# M100X.net
KiCad netlist of a schematic drawn in EAGLE
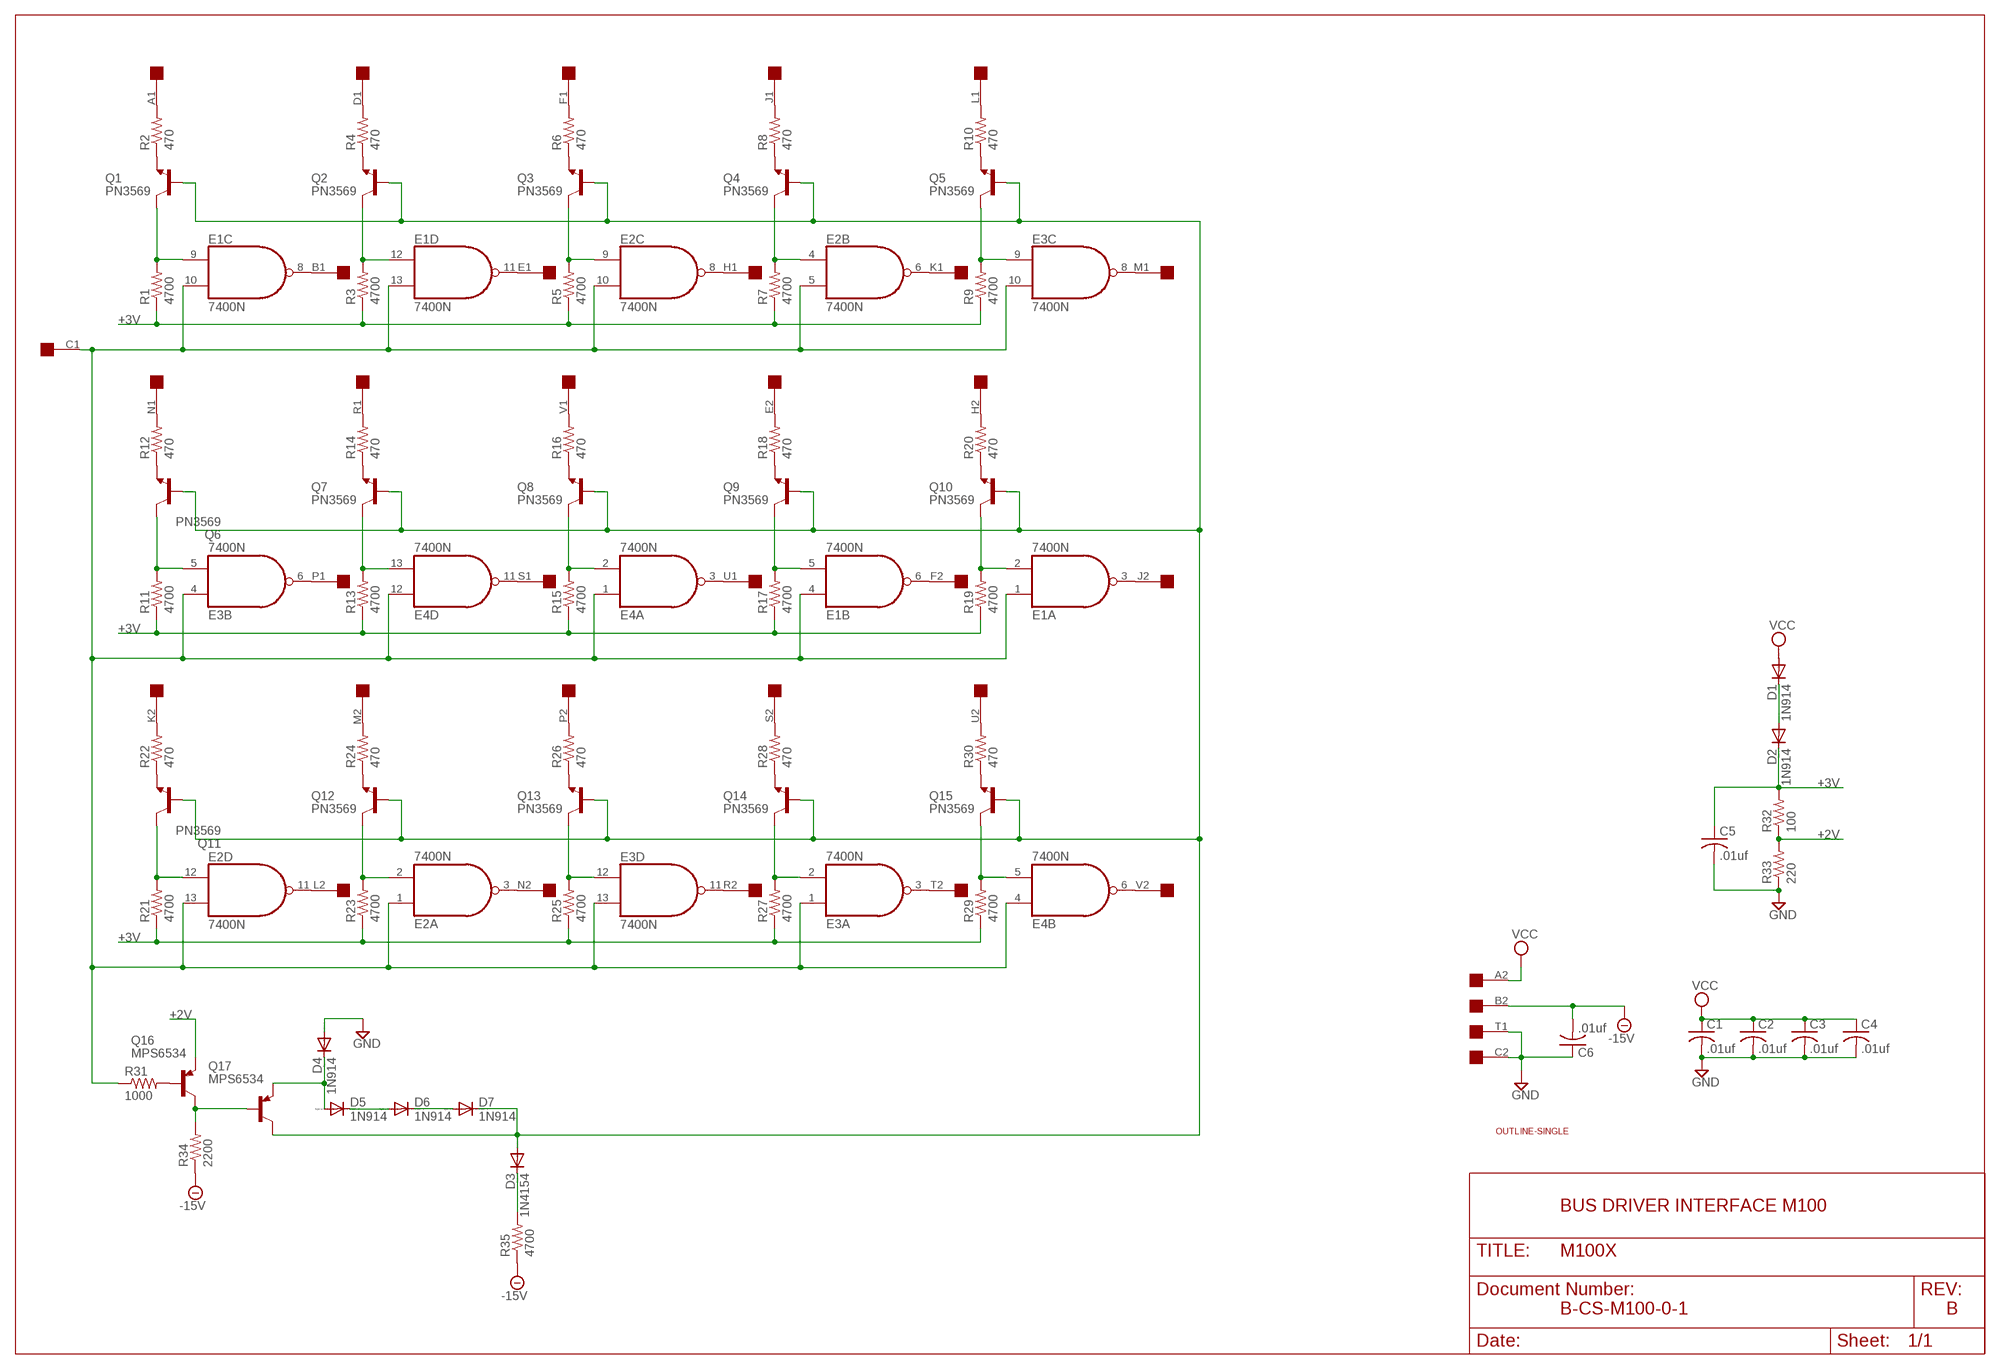
[diagram p0: schematic, sheet 1]

(export (version "E")
  (design (tool "Eeschema 10.0.6"))
  (components
    (comp (ref "C1")
      (value ".01uf")
      (footprint "eagle-import:C050-025X075")
      (libsource (lib "eagle-import") (part "C-US050-025X075"))
    )
    (comp (ref "C2")
      (value ".01uf")
      (footprint "eagle-import:C050-025X075")
      (libsource (lib "eagle-import") (part "C-US050-025X075"))
    )
    (comp (ref "C3")
      (value ".01uf")
      (footprint "eagle-import:C050-025X075")
      (libsource (lib "eagle-import") (part "C-US050-025X075"))
    )
    (comp (ref "C4")
      (value ".01uf")
      (footprint "eagle-import:C050-025X075")
      (libsource (lib "eagle-import") (part "C-US050-025X075"))
    )
    (comp (ref "C5")
      (value ".01uf")
      (footprint "eagle-import:C050-025X075")
      (libsource (lib "eagle-import") (part "C-US050-025X075"))
    )
    (comp (ref "C6")
      (value ".01uf")
      (footprint "eagle-import:C050-025X075")
      (libsource (lib "eagle-import") (part "C-US050-025X075"))
    )
    (comp (ref "D1")
      (value "1N914")
      (footprint "eagle-import:DO35-10")
      (libsource (lib "eagle-import") (part "1N4148DO35-10"))
    )
    (comp (ref "D2")
      (value "1N914")
      (footprint "eagle-import:DO35-10")
      (libsource (lib "eagle-import") (part "1N4148DO35-10"))
    )
    (comp (ref "D3")
      (value "1N4154")
      (footprint "eagle-import:DO35-10")
      (libsource (lib "eagle-import") (part "1N4148DO35-10"))
    )
    (comp (ref "D4")
      (value "1N914")
      (footprint "eagle-import:DO35-10")
      (libsource (lib "eagle-import") (part "1N4148DO35-10"))
    )
    (comp (ref "D5")
      (value "1N914")
      (footprint "eagle-import:DO35-10")
      (libsource (lib "eagle-import") (part "1N4148DO35-10"))
    )
    (comp (ref "D6")
      (value "1N914")
      (footprint "eagle-import:DO35-10")
      (libsource (lib "eagle-import") (part "1N4148DO35-10"))
    )
    (comp (ref "D7")
      (value "1N914")
      (footprint "eagle-import:DO35-10")
      (libsource (lib "eagle-import") (part "1N4148DO35-10"))
    )
    (comp (ref "E1")
      (value "7400N")
      (footprint "eagle-import:DIL14")
      (libsource (lib "eagle-import") (part "7400N"))
    )
    (comp (ref "E2")
      (value "7400N")
      (footprint "eagle-import:DIL14")
      (libsource (lib "eagle-import") (part "7400N"))
    )
    (comp (ref "E3")
      (value "7400N")
      (footprint "eagle-import:DIL14")
      (libsource (lib "eagle-import") (part "7400N"))
    )
    (comp (ref "E4")
      (value "7400N")
      (footprint "eagle-import:DIL14")
      (libsource (lib "eagle-import") (part "7400N"))
    )
    (comp (ref "Q1")
      (value "PN3569")
      (footprint "eagle-import:TO5")
      (libsource (lib "eagle-import") (part "2N2219"))
    )
    (comp (ref "Q2")
      (value "PN3569")
      (footprint "eagle-import:TO5")
      (libsource (lib "eagle-import") (part "2N2219"))
    )
    (comp (ref "Q3")
      (value "PN3569")
      (footprint "eagle-import:TO5")
      (libsource (lib "eagle-import") (part "2N2219"))
    )
    (comp (ref "Q4")
      (value "PN3569")
      (footprint "eagle-import:TO5")
      (libsource (lib "eagle-import") (part "2N2219"))
    )
    (comp (ref "Q5")
      (value "PN3569")
      (footprint "eagle-import:TO5")
      (libsource (lib "eagle-import") (part "2N2219"))
    )
    (comp (ref "Q6")
      (value "PN3569")
      (footprint "eagle-import:TO5")
      (libsource (lib "eagle-import") (part "2N2219"))
    )
    (comp (ref "Q7")
      (value "PN3569")
      (footprint "eagle-import:TO5")
      (libsource (lib "eagle-import") (part "2N2219"))
    )
    (comp (ref "Q8")
      (value "PN3569")
      (footprint "eagle-import:TO5")
      (libsource (lib "eagle-import") (part "2N2219"))
    )
    (comp (ref "Q9")
      (value "PN3569")
      (footprint "eagle-import:TO5")
      (libsource (lib "eagle-import") (part "2N2219"))
    )
    (comp (ref "Q10")
      (value "PN3569")
      (footprint "eagle-import:TO5")
      (libsource (lib "eagle-import") (part "2N2219"))
    )
    (comp (ref "Q11")
      (value "PN3569")
      (footprint "eagle-import:TO5")
      (libsource (lib "eagle-import") (part "2N2219"))
    )
    (comp (ref "Q12")
      (value "PN3569")
      (footprint "eagle-import:TO5")
      (libsource (lib "eagle-import") (part "2N2219"))
    )
    (comp (ref "Q13")
      (value "PN3569")
      (footprint "eagle-import:TO5")
      (libsource (lib "eagle-import") (part "2N2219"))
    )
    (comp (ref "Q14")
      (value "PN3569")
      (footprint "eagle-import:TO5")
      (libsource (lib "eagle-import") (part "2N2219"))
    )
    (comp (ref "Q15")
      (value "PN3569")
      (footprint "eagle-import:TO5")
      (libsource (lib "eagle-import") (part "2N2219"))
    )
    (comp (ref "Q16")
      (value "MPS6534")
      (footprint "eagle-import:TO5")
      (libsource (lib "eagle-import") (part "-PNP-TO5"))
    )
    (comp (ref "Q17")
      (value "MPS6534")
      (footprint "eagle-import:TO5")
      (libsource (lib "eagle-import") (part "-PNP-TO5"))
    )
    (comp (ref "R1")
      (value "4700")
      (footprint "eagle-import:0207_10")
      (libsource (lib "eagle-import") (part "R-US_0207/10"))
    )
    (comp (ref "R2")
      (value "470")
      (footprint "eagle-import:0207_10")
      (libsource (lib "eagle-import") (part "R-US_0207/10"))
    )
    (comp (ref "R3")
      (value "4700")
      (footprint "eagle-import:0207_10")
      (libsource (lib "eagle-import") (part "R-US_0207/10"))
    )
    (comp (ref "R4")
      (value "470")
      (footprint "eagle-import:0207_10")
      (libsource (lib "eagle-import") (part "R-US_0207/10"))
    )
    (comp (ref "R5")
      (value "4700")
      (footprint "eagle-import:0207_10")
      (libsource (lib "eagle-import") (part "R-US_0207/10"))
    )
    (comp (ref "R6")
      (value "470")
      (footprint "eagle-import:0207_10")
      (libsource (lib "eagle-import") (part "R-US_0207/10"))
    )
    (comp (ref "R7")
      (value "4700")
      (footprint "eagle-import:0207_10")
      (libsource (lib "eagle-import") (part "R-US_0207/10"))
    )
    (comp (ref "R8")
      (value "470")
      (footprint "eagle-import:0207_10")
      (libsource (lib "eagle-import") (part "R-US_0207/10"))
    )
    (comp (ref "R9")
      (value "4700")
      (footprint "eagle-import:0207_10")
      (libsource (lib "eagle-import") (part "R-US_0207/10"))
    )
    (comp (ref "R10")
      (value "470")
      (footprint "eagle-import:0207_10")
      (libsource (lib "eagle-import") (part "R-US_0207/10"))
    )
    (comp (ref "R11")
      (value "4700")
      (footprint "eagle-import:0207_10")
      (libsource (lib "eagle-import") (part "R-US_0207/10"))
    )
    (comp (ref "R12")
      (value "470")
      (footprint "eagle-import:0207_10")
      (libsource (lib "eagle-import") (part "R-US_0207/10"))
    )
    (comp (ref "R13")
      (value "4700")
      (footprint "eagle-import:0207_10")
      (libsource (lib "eagle-import") (part "R-US_0207/10"))
    )
    (comp (ref "R14")
      (value "470")
      (footprint "eagle-import:0207_10")
      (libsource (lib "eagle-import") (part "R-US_0207/10"))
    )
    (comp (ref "R15")
      (value "4700")
      (footprint "eagle-import:0207_10")
      (libsource (lib "eagle-import") (part "R-US_0207/10"))
    )
    (comp (ref "R16")
      (value "470")
      (footprint "eagle-import:0207_10")
      (libsource (lib "eagle-import") (part "R-US_0207/10"))
    )
    (comp (ref "R17")
      (value "4700")
      (footprint "eagle-import:0207_10")
      (libsource (lib "eagle-import") (part "R-US_0207/10"))
    )
    (comp (ref "R18")
      (value "470")
      (footprint "eagle-import:0207_10")
      (libsource (lib "eagle-import") (part "R-US_0207/10"))
    )
    (comp (ref "R19")
      (value "4700")
      (footprint "eagle-import:0207_10")
      (libsource (lib "eagle-import") (part "R-US_0207/10"))
    )
    (comp (ref "R20")
      (value "470")
      (footprint "eagle-import:0207_10")
      (libsource (lib "eagle-import") (part "R-US_0207/10"))
    )
    (comp (ref "R21")
      (value "4700")
      (footprint "eagle-import:0207_10")
      (libsource (lib "eagle-import") (part "R-US_0207/10"))
    )
    (comp (ref "R22")
      (value "470")
      (footprint "eagle-import:0207_10")
      (libsource (lib "eagle-import") (part "R-US_0207/10"))
    )
    (comp (ref "R23")
      (value "4700")
      (footprint "eagle-import:0207_10")
      (libsource (lib "eagle-import") (part "R-US_0207/10"))
    )
    (comp (ref "R24")
      (value "470")
      (footprint "eagle-import:0207_10")
      (libsource (lib "eagle-import") (part "R-US_0207/10"))
    )
    (comp (ref "R25")
      (value "4700")
      (footprint "eagle-import:0207_10")
      (libsource (lib "eagle-import") (part "R-US_0207/10"))
    )
    (comp (ref "R26")
      (value "470")
      (footprint "eagle-import:0207_10")
      (libsource (lib "eagle-import") (part "R-US_0207/10"))
    )
    (comp (ref "R27")
      (value "4700")
      (footprint "eagle-import:0207_10")
      (libsource (lib "eagle-import") (part "R-US_0207/10"))
    )
    (comp (ref "R28")
      (value "470")
      (footprint "eagle-import:0207_10")
      (libsource (lib "eagle-import") (part "R-US_0207/10"))
    )
    (comp (ref "R29")
      (value "4700")
      (footprint "eagle-import:0207_10")
      (libsource (lib "eagle-import") (part "R-US_0207/10"))
    )
    (comp (ref "R30")
      (value "470")
      (footprint "eagle-import:0207_10")
      (libsource (lib "eagle-import") (part "R-US_0207/10"))
    )
    (comp (ref "R31")
      (value "1000")
      (footprint "eagle-import:0207_10")
      (libsource (lib "eagle-import") (part "R-US_0207/10"))
    )
    (comp (ref "R32")
      (value "100")
      (footprint "eagle-import:0207_10")
      (libsource (lib "eagle-import") (part "R-US_0207/10"))
    )
    (comp (ref "R33")
      (value "220")
      (footprint "eagle-import:0207_10")
      (libsource (lib "eagle-import") (part "R-US_0207/10"))
    )
    (comp (ref "R34")
      (value "2200")
      (footprint "eagle-import:0207_10")
      (libsource (lib "eagle-import") (part "R-US_0207/10"))
    )
    (comp (ref "R35")
      (value "4700")
      (footprint "eagle-import:0207_10")
      (libsource (lib "eagle-import") (part "R-US_0207/10"))
    )
    (comp (ref "U$1")
      (value "SINGLE")
      (footprint "eagle-import:EDGE-CON2")
      (libsource (lib "eagle-import") (part "SINGLE"))
    )
    (comp (ref "U$2")
      (value "OUTLINE-SINGLE")
      (footprint "eagle-import:SINGLE")
      (libsource (lib "eagle-import") (part "OUTLINE-SINGLE"))
    )
  )
  (nets
    (net (code "1") (name "-15V") (class "Default")
      (node (ref "C6") (pin "2") (pinfunction "2_2") (pintype "passive"))
      (node (ref "R34") (pin "1") (pinfunction "1_1") (pintype "passive"))
      (node (ref "R35") (pin "1") (pinfunction "1_1") (pintype "passive"))
      (node (ref "U$1") (pin "B2") (pinfunction "1_B2") (pintype "bidirectional"))
    )
    (net (code "2") (name "/+2V") (class "Default")
      (node (ref "Q16") (pin "1") (pinfunction "E_1") (pintype "passive"))
      (node (ref "R32") (pin "1") (pinfunction "1_1") (pintype "passive"))
      (node (ref "R33") (pin "2") (pinfunction "2_2") (pintype "passive"))
    )
    (net (code "3") (name "/+3V") (class "Default")
      (node (ref "C5") (pin "1") (pinfunction "1_1") (pintype "passive"))
      (node (ref "D2") (pin "C") (pinfunction "C_C") (pintype "passive"))
      (node (ref "R1") (pin "1") (pinfunction "1_1") (pintype "passive"))
      (node (ref "R11") (pin "1") (pinfunction "1_1") (pintype "passive"))
      (node (ref "R13") (pin "1") (pinfunction "1_1") (pintype "passive"))
      (node (ref "R15") (pin "1") (pinfunction "1_1") (pintype "passive"))
      (node (ref "R17") (pin "1") (pinfunction "1_1") (pintype "passive"))
      (node (ref "R19") (pin "1") (pinfunction "1_1") (pintype "passive"))
      (node (ref "R21") (pin "1") (pinfunction "1_1") (pintype "passive"))
      (node (ref "R23") (pin "1") (pinfunction "1_1") (pintype "passive"))
      (node (ref "R25") (pin "1") (pinfunction "1_1") (pintype "passive"))
      (node (ref "R27") (pin "1") (pinfunction "1_1") (pintype "passive"))
      (node (ref "R29") (pin "1") (pinfunction "1_1") (pintype "passive"))
      (node (ref "R3") (pin "1") (pinfunction "1_1") (pintype "passive"))
      (node (ref "R32") (pin "2") (pinfunction "2_2") (pintype "passive"))
      (node (ref "R5") (pin "1") (pinfunction "1_1") (pintype "passive"))
      (node (ref "R7") (pin "1") (pinfunction "1_1") (pintype "passive"))
      (node (ref "R9") (pin "1") (pinfunction "1_1") (pintype "passive"))
    )
    (net (code "4") (name "GND") (class "Default")
      (node (ref "C1") (pin "2") (pinfunction "2_2") (pintype "passive"))
      (node (ref "C2") (pin "2") (pinfunction "2_2") (pintype "passive"))
      (node (ref "C3") (pin "2") (pinfunction "2_2") (pintype "passive"))
      (node (ref "C4") (pin "2") (pinfunction "2_2") (pintype "passive"))
      (node (ref "C5") (pin "2") (pinfunction "2_2") (pintype "passive"))
      (node (ref "C6") (pin "1") (pinfunction "1_1") (pintype "passive"))
      (node (ref "D4") (pin "A") (pinfunction "A_A") (pintype "passive"))
      (node (ref "R33") (pin "1") (pinfunction "1_1") (pintype "passive"))
      (node (ref "U$1") (pin "C2") (pinfunction "1_C2") (pintype "bidirectional"))
      (node (ref "U$1") (pin "T1") (pinfunction "1_T1") (pintype "bidirectional"))
    )
    (net (code "5") (name "Net-(D1-PadC)") (class "Default")
      (node (ref "D1") (pin "C") (pinfunction "C_C") (pintype "passive"))
      (node (ref "D2") (pin "A") (pinfunction "A_A") (pintype "passive"))
    )
    (net (code "6") (name "Net-(D3-PadC)") (class "Default")
      (node (ref "D3") (pin "C") (pinfunction "C_C") (pintype "passive"))
      (node (ref "R35") (pin "2") (pinfunction "2_2") (pintype "passive"))
    )
    (net (code "7") (name "Net-(D5-PadC)") (class "Default")
      (node (ref "D5") (pin "C") (pinfunction "C_C") (pintype "passive"))
      (node (ref "D6") (pin "A") (pinfunction "A_A") (pintype "passive"))
    )
    (net (code "8") (name "Net-(D6-PadC)") (class "Default")
      (node (ref "D6") (pin "C") (pinfunction "C_C") (pintype "passive"))
      (node (ref "D7") (pin "A") (pinfunction "A_A") (pintype "passive"))
    )
    (net (code "9") (name "Net-(E1A-I0)") (class "Default")
      (node (ref "E1") (pin "1") (pinfunction "I0_1") (pintype "input"))
      (node (ref "E1") (pin "10") (pinfunction "I1_10") (pintype "input"))
      (node (ref "E1") (pin "13") (pinfunction "I1_13") (pintype "input"))
      (node (ref "E1") (pin "4") (pinfunction "I0_4") (pintype "input"))
      (node (ref "E2") (pin "1") (pinfunction "I0_1") (pintype "input"))
      (node (ref "E2") (pin "10") (pinfunction "I1_10") (pintype "input"))
      (node (ref "E2") (pin "13") (pinfunction "I1_13") (pintype "input"))
      (node (ref "E2") (pin "5") (pinfunction "I1_5") (pintype "input"))
      (node (ref "E3") (pin "1") (pinfunction "I0_1") (pintype "input"))
      (node (ref "E3") (pin "10") (pinfunction "I1_10") (pintype "input"))
      (node (ref "E3") (pin "13") (pinfunction "I1_13") (pintype "input"))
      (node (ref "E3") (pin "4") (pinfunction "I0_4") (pintype "input"))
      (node (ref "E4") (pin "1") (pinfunction "I0_1") (pintype "input"))
      (node (ref "E4") (pin "12") (pinfunction "I0_12") (pintype "input"))
      (node (ref "E4") (pin "4") (pinfunction "I0_4") (pintype "input"))
      (node (ref "R31") (pin "1") (pinfunction "1_1") (pintype "passive"))
      (node (ref "U$1") (pin "C1") (pinfunction "1_C1") (pintype "bidirectional"))
    )
    (net (code "10") (name "Net-(E1A-I1)") (class "Default")
      (node (ref "E1") (pin "2") (pinfunction "I1_2") (pintype "input"))
      (node (ref "Q10") (pin "3") (pinfunction "C_3") (pintype "passive"))
      (node (ref "R19") (pin "2") (pinfunction "2_2") (pintype "passive"))
    )
    (net (code "11") (name "Net-(E1A-O)") (class "Default")
      (node (ref "E1") (pin "3") (pinfunction "O_3") (pintype "output"))
      (node (ref "U$1") (pin "J2") (pinfunction "1_J2") (pintype "bidirectional"))
    )
    (net (code "12") (name "Net-(E1B-I1)") (class "Default")
      (node (ref "E1") (pin "5") (pinfunction "I1_5") (pintype "input"))
      (node (ref "Q9") (pin "3") (pinfunction "C_3") (pintype "passive"))
      (node (ref "R17") (pin "2") (pinfunction "2_2") (pintype "passive"))
    )
    (net (code "13") (name "Net-(E1B-O)") (class "Default")
      (node (ref "E1") (pin "6") (pinfunction "O_6") (pintype "output"))
      (node (ref "U$1") (pin "F2") (pinfunction "1_F2") (pintype "bidirectional"))
    )
    (net (code "14") (name "Net-(E1C-I0)") (class "Default")
      (node (ref "E1") (pin "9") (pinfunction "I0_9") (pintype "input"))
      (node (ref "Q1") (pin "3") (pinfunction "C_3") (pintype "passive"))
      (node (ref "R1") (pin "2") (pinfunction "2_2") (pintype "passive"))
    )
    (net (code "15") (name "Net-(E1C-O)") (class "Default")
      (node (ref "E1") (pin "8") (pinfunction "O_8") (pintype "output"))
      (node (ref "U$1") (pin "B1") (pinfunction "1_B1") (pintype "bidirectional"))
    )
    (net (code "16") (name "Net-(E1D-I0)") (class "Default")
      (node (ref "E1") (pin "12") (pinfunction "I0_12") (pintype "input"))
      (node (ref "Q2") (pin "3") (pinfunction "C_3") (pintype "passive"))
      (node (ref "R3") (pin "2") (pinfunction "2_2") (pintype "passive"))
    )
    (net (code "17") (name "Net-(E1D-O)") (class "Default")
      (node (ref "E1") (pin "11") (pinfunction "O_11") (pintype "output"))
      (node (ref "U$1") (pin "E1") (pinfunction "1_E1") (pintype "bidirectional"))
    )
    (net (code "18") (name "Net-(E2A-I1)") (class "Default")
      (node (ref "E2") (pin "2") (pinfunction "I1_2") (pintype "input"))
      (node (ref "Q12") (pin "3") (pinfunction "C_3") (pintype "passive"))
      (node (ref "R23") (pin "2") (pinfunction "2_2") (pintype "passive"))
    )
    (net (code "19") (name "Net-(E2A-O)") (class "Default")
      (node (ref "E2") (pin "3") (pinfunction "O_3") (pintype "output"))
      (node (ref "U$1") (pin "N2") (pinfunction "1_N2") (pintype "bidirectional"))
    )
    (net (code "20") (name "Net-(E2B-I0)") (class "Default")
      (node (ref "E2") (pin "4") (pinfunction "I0_4") (pintype "input"))
      (node (ref "Q4") (pin "3") (pinfunction "C_3") (pintype "passive"))
      (node (ref "R7") (pin "2") (pinfunction "2_2") (pintype "passive"))
    )
    (net (code "21") (name "Net-(E2B-O)") (class "Default")
      (node (ref "E2") (pin "6") (pinfunction "O_6") (pintype "output"))
      (node (ref "U$1") (pin "K1") (pinfunction "1_K1") (pintype "bidirectional"))
    )
    (net (code "22") (name "Net-(E2C-I0)") (class "Default")
      (node (ref "E2") (pin "9") (pinfunction "I0_9") (pintype "input"))
      (node (ref "Q3") (pin "3") (pinfunction "C_3") (pintype "passive"))
      (node (ref "R5") (pin "2") (pinfunction "2_2") (pintype "passive"))
    )
    (net (code "23") (name "Net-(E2C-O)") (class "Default")
      (node (ref "E2") (pin "8") (pinfunction "O_8") (pintype "output"))
      (node (ref "U$1") (pin "H1") (pinfunction "1_H1") (pintype "bidirectional"))
    )
    (net (code "24") (name "Net-(E2D-I0)") (class "Default")
      (node (ref "E2") (pin "12") (pinfunction "I0_12") (pintype "input"))
      (node (ref "Q11") (pin "3") (pinfunction "C_3") (pintype "passive"))
      (node (ref "R21") (pin "2") (pinfunction "2_2") (pintype "passive"))
    )
    (net (code "25") (name "Net-(E2D-O)") (class "Default")
      (node (ref "E2") (pin "11") (pinfunction "O_11") (pintype "output"))
      (node (ref "U$1") (pin "L2") (pinfunction "1_L2") (pintype "bidirectional"))
    )
    (net (code "26") (name "Net-(E3A-I1)") (class "Default")
      (node (ref "E3") (pin "2") (pinfunction "I1_2") (pintype "input"))
      (node (ref "Q14") (pin "3") (pinfunction "C_3") (pintype "passive"))
      (node (ref "R27") (pin "2") (pinfunction "2_2") (pintype "passive"))
    )
    (net (code "27") (name "Net-(E3A-O)") (class "Default")
      (node (ref "E3") (pin "3") (pinfunction "O_3") (pintype "output"))
      (node (ref "U$1") (pin "T2") (pinfunction "1_T2") (pintype "bidirectional"))
    )
    (net (code "28") (name "Net-(E3B-I1)") (class "Default")
      (node (ref "E3") (pin "5") (pinfunction "I1_5") (pintype "input"))
      (node (ref "Q6") (pin "3") (pinfunction "C_3") (pintype "passive"))
      (node (ref "R11") (pin "2") (pinfunction "2_2") (pintype "passive"))
    )
    (net (code "29") (name "Net-(E3B-O)") (class "Default")
      (node (ref "E3") (pin "6") (pinfunction "O_6") (pintype "output"))
      (node (ref "U$1") (pin "P1") (pinfunction "1_P1") (pintype "bidirectional"))
    )
    (net (code "30") (name "Net-(E3C-I0)") (class "Default")
      (node (ref "E3") (pin "9") (pinfunction "I0_9") (pintype "input"))
      (node (ref "Q5") (pin "3") (pinfunction "C_3") (pintype "passive"))
      (node (ref "R9") (pin "2") (pinfunction "2_2") (pintype "passive"))
    )
    (net (code "31") (name "Net-(E3C-O)") (class "Default")
      (node (ref "E3") (pin "8") (pinfunction "O_8") (pintype "output"))
      (node (ref "U$1") (pin "M1") (pinfunction "1_M1") (pintype "bidirectional"))
    )
    (net (code "32") (name "Net-(E3D-I0)") (class "Default")
      (node (ref "E3") (pin "12") (pinfunction "I0_12") (pintype "input"))
      (node (ref "Q13") (pin "3") (pinfunction "C_3") (pintype "passive"))
      (node (ref "R25") (pin "2") (pinfunction "2_2") (pintype "passive"))
    )
    (net (code "33") (name "Net-(E3D-O)") (class "Default")
      (node (ref "E3") (pin "11") (pinfunction "O_11") (pintype "output"))
      (node (ref "U$1") (pin "R2") (pinfunction "1_R2") (pintype "bidirectional"))
    )
    (net (code "34") (name "Net-(E4A-I1)") (class "Default")
      (node (ref "E4") (pin "2") (pinfunction "I1_2") (pintype "input"))
      (node (ref "Q8") (pin "3") (pinfunction "C_3") (pintype "passive"))
      (node (ref "R15") (pin "2") (pinfunction "2_2") (pintype "passive"))
    )
    (net (code "35") (name "Net-(E4A-O)") (class "Default")
      (node (ref "E4") (pin "3") (pinfunction "O_3") (pintype "output"))
      (node (ref "U$1") (pin "U1") (pinfunction "1_U1") (pintype "bidirectional"))
    )
    (net (code "36") (name "Net-(E4B-I1)") (class "Default")
      (node (ref "E4") (pin "5") (pinfunction "I1_5") (pintype "input"))
      (node (ref "Q15") (pin "3") (pinfunction "C_3") (pintype "passive"))
      (node (ref "R29") (pin "2") (pinfunction "2_2") (pintype "passive"))
    )
    (net (code "37") (name "Net-(E4B-O)") (class "Default")
      (node (ref "E4") (pin "6") (pinfunction "O_6") (pintype "output"))
      (node (ref "U$1") (pin "V2") (pinfunction "1_V2") (pintype "bidirectional"))
    )
    (net (code "38") (name "Net-(E4D-I1)") (class "Default")
      (node (ref "E4") (pin "13") (pinfunction "I1_13") (pintype "input"))
      (node (ref "Q7") (pin "3") (pinfunction "C_3") (pintype "passive"))
      (node (ref "R13") (pin "2") (pinfunction "2_2") (pintype "passive"))
    )
    (net (code "39") (name "Net-(E4D-O)") (class "Default")
      (node (ref "E4") (pin "11") (pinfunction "O_11") (pintype "output"))
      (node (ref "U$1") (pin "S1") (pinfunction "1_S1") (pintype "bidirectional"))
    )
    (net (code "40") (name "Net-(Q1-B)") (class "Default")
      (node (ref "D3") (pin "A") (pinfunction "A_A") (pintype "passive"))
      (node (ref "D7") (pin "C") (pinfunction "C_C") (pintype "passive"))
      (node (ref "Q1") (pin "2") (pinfunction "B_2") (pintype "passive"))
      (node (ref "Q10") (pin "2") (pinfunction "B_2") (pintype "passive"))
      (node (ref "Q11") (pin "2") (pinfunction "B_2") (pintype "passive"))
      (node (ref "Q12") (pin "2") (pinfunction "B_2") (pintype "passive"))
      (node (ref "Q13") (pin "2") (pinfunction "B_2") (pintype "passive"))
      (node (ref "Q14") (pin "2") (pinfunction "B_2") (pintype "passive"))
      (node (ref "Q15") (pin "2") (pinfunction "B_2") (pintype "passive"))
      (node (ref "Q17") (pin "3") (pinfunction "C_3") (pintype "passive"))
      (node (ref "Q2") (pin "2") (pinfunction "B_2") (pintype "passive"))
      (node (ref "Q3") (pin "2") (pinfunction "B_2") (pintype "passive"))
      (node (ref "Q4") (pin "2") (pinfunction "B_2") (pintype "passive"))
      (node (ref "Q5") (pin "2") (pinfunction "B_2") (pintype "passive"))
      (node (ref "Q6") (pin "2") (pinfunction "B_2") (pintype "passive"))
      (node (ref "Q7") (pin "2") (pinfunction "B_2") (pintype "passive"))
      (node (ref "Q8") (pin "2") (pinfunction "B_2") (pintype "passive"))
      (node (ref "Q9") (pin "2") (pinfunction "B_2") (pintype "passive"))
    )
    (net (code "41") (name "Net-(Q1-E)") (class "Default")
      (node (ref "Q1") (pin "1") (pinfunction "E_1") (pintype "passive"))
      (node (ref "R2") (pin "1") (pinfunction "1_1") (pintype "passive"))
    )
    (net (code "42") (name "Net-(Q2-E)") (class "Default")
      (node (ref "Q2") (pin "1") (pinfunction "E_1") (pintype "passive"))
      (node (ref "R4") (pin "1") (pinfunction "1_1") (pintype "passive"))
    )
    (net (code "43") (name "Net-(Q3-E)") (class "Default")
      (node (ref "Q3") (pin "1") (pinfunction "E_1") (pintype "passive"))
      (node (ref "R6") (pin "1") (pinfunction "1_1") (pintype "passive"))
    )
    (net (code "44") (name "Net-(Q4-E)") (class "Default")
      (node (ref "Q4") (pin "1") (pinfunction "E_1") (pintype "passive"))
      (node (ref "R8") (pin "1") (pinfunction "1_1") (pintype "passive"))
    )
    (net (code "45") (name "Net-(Q5-E)") (class "Default")
      (node (ref "Q5") (pin "1") (pinfunction "E_1") (pintype "passive"))
      (node (ref "R10") (pin "1") (pinfunction "1_1") (pintype "passive"))
    )
    (net (code "46") (name "Net-(Q6-E)") (class "Default")
      (node (ref "Q6") (pin "1") (pinfunction "E_1") (pintype "passive"))
      (node (ref "R12") (pin "1") (pinfunction "1_1") (pintype "passive"))
    )
    (net (code "47") (name "Net-(Q7-E)") (class "Default")
      (node (ref "Q7") (pin "1") (pinfunction "E_1") (pintype "passive"))
      (node (ref "R14") (pin "1") (pinfunction "1_1") (pintype "passive"))
    )
    (net (code "48") (name "Net-(Q8-E)") (class "Default")
      (node (ref "Q8") (pin "1") (pinfunction "E_1") (pintype "passive"))
      (node (ref "R16") (pin "1") (pinfunction "1_1") (pintype "passive"))
    )
    (net (code "49") (name "Net-(Q9-E)") (class "Default")
      (node (ref "Q9") (pin "1") (pinfunction "E_1") (pintype "passive"))
      (node (ref "R18") (pin "1") (pinfunction "1_1") (pintype "passive"))
    )
    (net (code "50") (name "Net-(Q10-E)") (class "Default")
      (node (ref "Q10") (pin "1") (pinfunction "E_1") (pintype "passive"))
      (node (ref "R20") (pin "1") (pinfunction "1_1") (pintype "passive"))
    )
    (net (code "51") (name "Net-(Q11-E)") (class "Default")
      (node (ref "Q11") (pin "1") (pinfunction "E_1") (pintype "passive"))
      (node (ref "R22") (pin "1") (pinfunction "1_1") (pintype "passive"))
    )
    (net (code "52") (name "Net-(Q12-E)") (class "Default")
      (node (ref "Q12") (pin "1") (pinfunction "E_1") (pintype "passive"))
      (node (ref "R24") (pin "1") (pinfunction "1_1") (pintype "passive"))
    )
    (net (code "53") (name "Net-(Q13-E)") (class "Default")
      (node (ref "Q13") (pin "1") (pinfunction "E_1") (pintype "passive"))
      (node (ref "R26") (pin "1") (pinfunction "1_1") (pintype "passive"))
    )
    (net (code "54") (name "Net-(Q14-E)") (class "Default")
      (node (ref "Q14") (pin "1") (pinfunction "E_1") (pintype "passive"))
      (node (ref "R28") (pin "1") (pinfunction "1_1") (pintype "passive"))
    )
    (net (code "55") (name "Net-(Q15-E)") (class "Default")
      (node (ref "Q15") (pin "1") (pinfunction "E_1") (pintype "passive"))
      (node (ref "R30") (pin "1") (pinfunction "1_1") (pintype "passive"))
    )
    (net (code "56") (name "Net-(Q16-B)") (class "Default")
      (node (ref "Q16") (pin "2") (pinfunction "B_2") (pintype "passive"))
      (node (ref "R31") (pin "2") (pinfunction "2_2") (pintype "passive"))
    )
    (net (code "57") (name "Net-(Q16-C)") (class "Default")
      (node (ref "Q16") (pin "3") (pinfunction "C_3") (pintype "passive"))
      (node (ref "Q17") (pin "2") (pinfunction "B_2") (pintype "passive"))
      (node (ref "R34") (pin "2") (pinfunction "2_2") (pintype "passive"))
    )
    (net (code "58") (name "Net-(Q17-E)") (class "Default")
      (node (ref "D4") (pin "C") (pinfunction "C_C") (pintype "passive"))
      (node (ref "D5") (pin "A") (pinfunction "A_A") (pintype "passive"))
      (node (ref "Q17") (pin "1") (pinfunction "E_1") (pintype "passive"))
    )
    (net (code "59") (name "Net-(U$1A-1)") (class "Default")
      (node (ref "R2") (pin "2") (pinfunction "2_2") (pintype "passive"))
      (node (ref "U$1") (pin "A1") (pinfunction "1_A1") (pintype "bidirectional"))
    )
    (net (code "60") (name "Net-(U$1AA-1)") (class "Default")
      (node (ref "R14") (pin "2") (pinfunction "2_2") (pintype "passive"))
      (node (ref "U$1") (pin "R1") (pinfunction "1_R1") (pintype "bidirectional"))
    )
    (net (code "61") (name "Net-(U$1AD-1)") (class "Default")
      (node (ref "R28") (pin "2") (pinfunction "2_2") (pintype "passive"))
      (node (ref "U$1") (pin "S2") (pinfunction "1_S2") (pintype "bidirectional"))
    )
    (net (code "62") (name "Net-(U$1AH-1)") (class "Default")
      (node (ref "R30") (pin "2") (pinfunction "2_2") (pintype "passive"))
      (node (ref "U$1") (pin "U2") (pinfunction "1_U2") (pintype "bidirectional"))
    )
    (net (code "63") (name "Net-(U$1AI-1)") (class "Default")
      (node (ref "R16") (pin "2") (pinfunction "2_2") (pintype "passive"))
      (node (ref "U$1") (pin "V1") (pinfunction "1_V1") (pintype "bidirectional"))
    )
    (net (code "64") (name "Net-(U$1G-1)") (class "Default")
      (node (ref "R4") (pin "2") (pinfunction "2_2") (pintype "passive"))
      (node (ref "U$1") (pin "D1") (pinfunction "1_D1") (pintype "bidirectional"))
    )
    (net (code "65") (name "Net-(U$1J-1)") (class "Default")
      (node (ref "R18") (pin "2") (pinfunction "2_2") (pintype "passive"))
      (node (ref "U$1") (pin "E2") (pinfunction "1_E2") (pintype "bidirectional"))
    )
    (net (code "66") (name "Net-(U$1K-1)") (class "Default")
      (node (ref "R6") (pin "2") (pinfunction "2_2") (pintype "passive"))
      (node (ref "U$1") (pin "F1") (pinfunction "1_F1") (pintype "bidirectional"))
    )
    (net (code "67") (name "Net-(U$1N-1)") (class "Default")
      (node (ref "R20") (pin "2") (pinfunction "2_2") (pintype "passive"))
      (node (ref "U$1") (pin "H2") (pinfunction "1_H2") (pintype "bidirectional"))
    )
    (net (code "68") (name "Net-(U$1O-1)") (class "Default")
      (node (ref "R8") (pin "2") (pinfunction "2_2") (pintype "passive"))
      (node (ref "U$1") (pin "J1") (pinfunction "1_J1") (pintype "bidirectional"))
    )
    (net (code "69") (name "Net-(U$1R-1)") (class "Default")
      (node (ref "R22") (pin "2") (pinfunction "2_2") (pintype "passive"))
      (node (ref "U$1") (pin "K2") (pinfunction "1_K2") (pintype "bidirectional"))
    )
    (net (code "70") (name "Net-(U$1S-1)") (class "Default")
      (node (ref "R10") (pin "2") (pinfunction "2_2") (pintype "passive"))
      (node (ref "U$1") (pin "L1") (pinfunction "1_L1") (pintype "bidirectional"))
    )
    (net (code "71") (name "Net-(U$1V-1)") (class "Default")
      (node (ref "R24") (pin "2") (pinfunction "2_2") (pintype "passive"))
      (node (ref "U$1") (pin "M2") (pinfunction "1_M2") (pintype "bidirectional"))
    )
    (net (code "72") (name "Net-(U$1W-1)") (class "Default")
      (node (ref "R12") (pin "2") (pinfunction "2_2") (pintype "passive"))
      (node (ref "U$1") (pin "N1") (pinfunction "1_N1") (pintype "bidirectional"))
    )
    (net (code "73") (name "Net-(U$1Z-1)") (class "Default")
      (node (ref "R26") (pin "2") (pinfunction "2_2") (pintype "passive"))
      (node (ref "U$1") (pin "P2") (pinfunction "1_P2") (pintype "bidirectional"))
    )
    (net (code "74") (name "VCC") (class "Default")
      (node (ref "C1") (pin "1") (pinfunction "1_1") (pintype "passive"))
      (node (ref "C2") (pin "1") (pinfunction "1_1") (pintype "passive"))
      (node (ref "C3") (pin "1") (pinfunction "1_1") (pintype "passive"))
      (node (ref "C4") (pin "1") (pinfunction "1_1") (pintype "passive"))
      (node (ref "D1") (pin "A") (pinfunction "A_A") (pintype "passive"))
      (node (ref "U$1") (pin "A2") (pinfunction "1_A2") (pintype "bidirectional"))
    )
  )
)
